# ShieldArduino_Due_5.net
KiCad netlist of a schematic drawn in Altium Designer
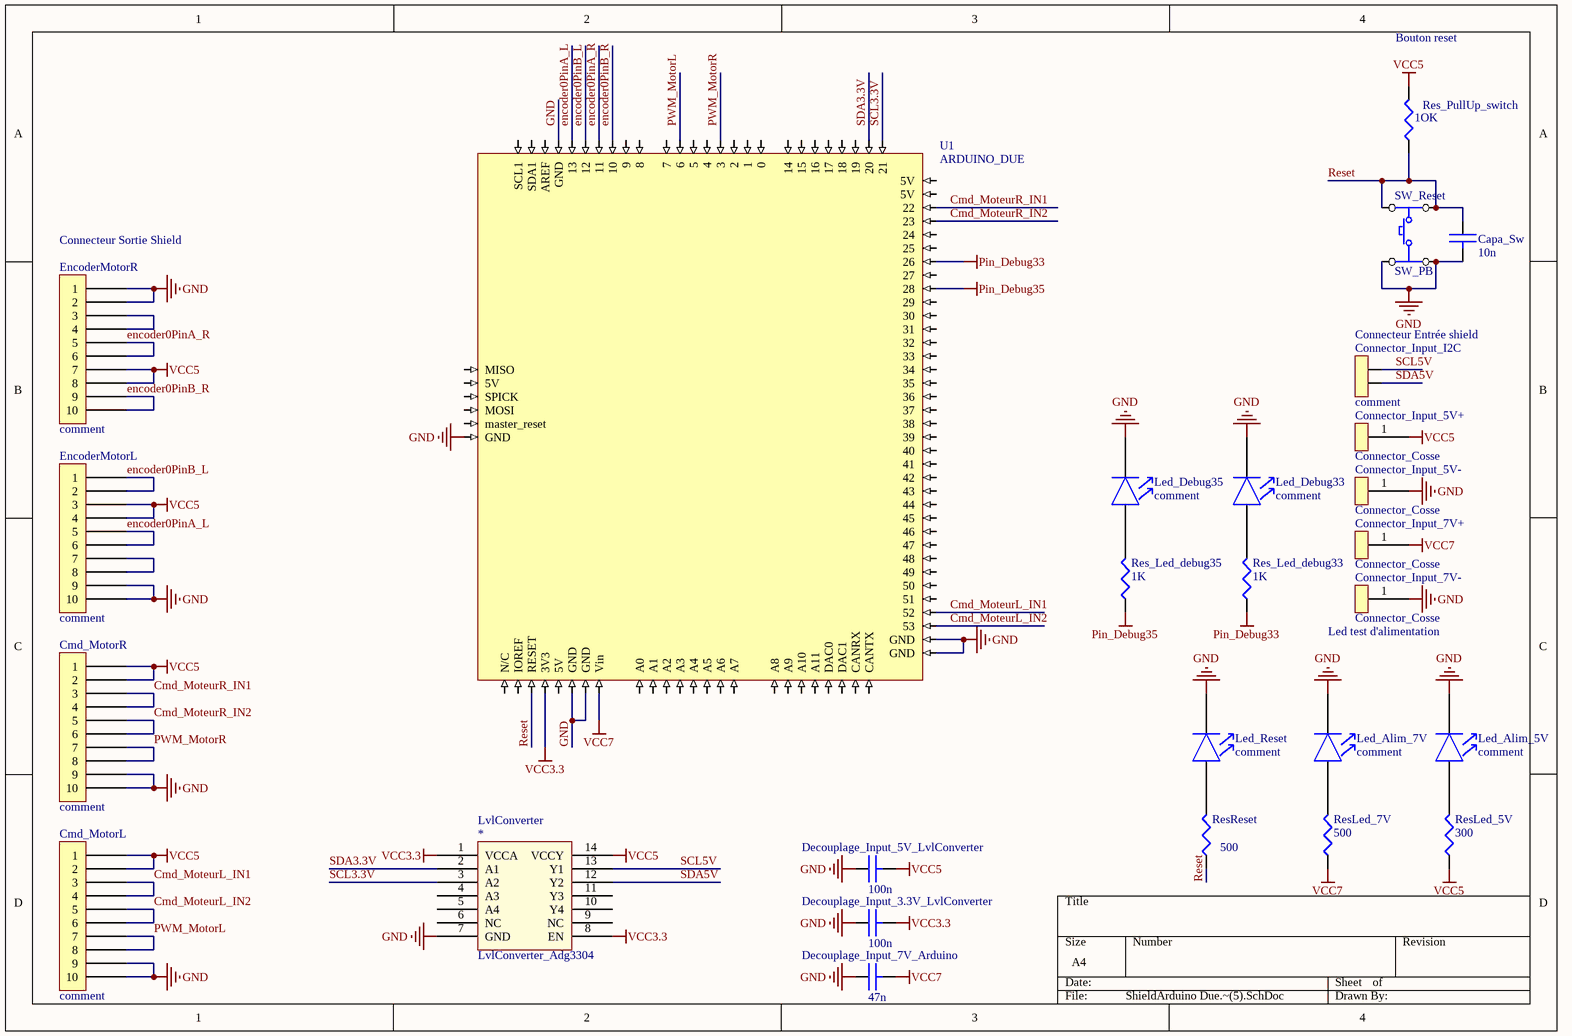
[diagram p0: ShieldArduino Due.~(5).SchDoc]

(export (version "E")
  (design (tool "Eeschema 10.0.6"))
  (components
    (comp (ref "*")
      (value "LvlConverter_Adg3304")
      (footprint "LvlConverter_Adg3304")
      (libsource (lib "LvlConverter_Adg3304") (part "LvlConverter_Adg3304"))
    )
    (comp (ref "Capa_Sw")
      (value "10n")
      (footprint "0805")
      (description "capacité non polarisée")
      (fields (field (name "Comment") "CAP"))
      (libsource (lib "ISEN_basics") (part "CAP"))
    )
    (comp (ref "Cmd_MotorL")
      (value "comment")
      (footprint "HE10-10V")
      (description "10-pin connector")
      (libsource (lib "ISEN_basics") (part "HE10-10"))
    )
    (comp (ref "Cmd_MotorR")
      (value "comment")
      (footprint "HE10-10V")
      (description "10-pin connector")
      (libsource (lib "ISEN_basics") (part "HE10-10"))
    )
    (comp (ref "Connector_Input_5V+")
      (value "Connector_Cosse")
      (footprint "Connector_Cosse")
      (libsource (lib "Connector_Cosse") (part "Connector_Cosse"))
    )
    (comp (ref "Connector_Input_5V-")
      (value "Connector_Cosse")
      (footprint "Connector_Cosse")
      (libsource (lib "Connector_Cosse") (part "Connector_Cosse"))
    )
    (comp (ref "Connector_Input_7V+")
      (value "Connector_Cosse")
      (footprint "Connector_Cosse")
      (libsource (lib "Connector_Cosse") (part "Connector_Cosse"))
    )
    (comp (ref "Connector_Input_7V-")
      (value "Connector_Cosse")
      (footprint "Connector_Cosse")
      (libsource (lib "Connector_Cosse") (part "Connector_Cosse"))
    )
    (comp (ref "Connector_Input_I2C")
      (value "comment")
      (footprint "AMP_2")
      (description "connecteur alim 2 pôles")
      (libsource (lib "ISEN_basics") (part "POWER2"))
    )
    (comp (ref "Decouplage_Input_3.3V_LvlConverter")
      (value "100n")
      (footprint "0805")
      (description "capacité non polarisée")
      (fields (field (name "Comment") "CAP"))
      (libsource (lib "ISEN_basics") (part "CAP"))
    )
    (comp (ref "Decouplage_Input_5V_LvlConverter")
      (value "100n")
      (footprint "0805")
      (description "capacité non polarisée")
      (fields (field (name "Comment") "CAP"))
      (libsource (lib "ISEN_basics") (part "CAP"))
    )
    (comp (ref "Decouplage_Input_7V_Arduino")
      (value "47n")
      (footprint "0805")
      (description "capacité non polarisée")
      (fields (field (name "Comment") "CAP"))
      (libsource (lib "ISEN_basics") (part "CAP"))
    )
    (comp (ref "EncoderMotorL")
      (value "comment")
      (footprint "HE10-10V")
      (description "10-pin connector")
      (libsource (lib "ISEN_basics") (part "HE10-10"))
    )
    (comp (ref "EncoderMotorR")
      (value "comment")
      (footprint "HE10-10V")
      (description "10-pin connector")
      (libsource (lib "ISEN_basics") (part "HE10-10"))
    )
    (comp (ref "Led_Alim_5V")
      (value "comment")
      (footprint "LED0805")
      (description "LED 5mm/3mm/CMS")
      (libsource (lib "ISEN_basics") (part "LED"))
    )
    (comp (ref "Led_Alim_7V")
      (value "comment")
      (footprint "LED0805")
      (description "LED 5mm/3mm/CMS")
      (libsource (lib "ISEN_basics") (part "LED"))
    )
    (comp (ref "Led_Debug33")
      (value "comment")
      (footprint "LED0805")
      (description "LED 5mm/3mm/CMS")
      (libsource (lib "ISEN_basics") (part "LED"))
    )
    (comp (ref "Led_Debug35")
      (value "comment")
      (footprint "LED0805")
      (description "LED 5mm/3mm/CMS")
      (libsource (lib "ISEN_basics") (part "LED"))
    )
    (comp (ref "Led_Reset")
      (value "comment")
      (footprint "LED0805")
      (description "LED 5mm/3mm/CMS")
      (libsource (lib "ISEN_basics") (part "LED"))
    )
    (comp (ref "ResLed_5V")
      (value "300")
      (footprint "0805")
      (description "resistance")
      (fields (field (name "Comment") "RES"))
      (libsource (lib "ISEN_basics") (part "RES"))
    )
    (comp (ref "ResLed_7V")
      (value "500")
      (footprint "0805")
      (description "resistance")
      (fields (field (name "Comment") "RES"))
      (libsource (lib "ISEN_basics") (part "RES"))
    )
    (comp (ref "ResReset")
      (value "500")
      (footprint "0805")
      (description "resistance")
      (fields (field (name "Comment") "RES"))
      (libsource (lib "ISEN_basics") (part "RES"))
    )
    (comp (ref "Res_Led_debug33")
      (value "1K")
      (footprint "0805")
      (description "resistance")
      (fields (field (name "Comment") "RES"))
      (libsource (lib "ISEN_basics") (part "RES"))
    )
    (comp (ref "Res_Led_debug35")
      (value "1K")
      (footprint "0805")
      (description "resistance")
      (fields (field (name "Comment") "RES"))
      (libsource (lib "ISEN_basics") (part "RES"))
    )
    (comp (ref "Res_PullUp_switch")
      (value "1OK")
      (footprint "0805")
      (description "resistance")
      (fields (field (name "Comment") "RES"))
      (libsource (lib "ISEN_basics") (part "RES"))
    )
    (comp (ref "SW_Reset") (value "SW_PB") (footprint "KSA") (libsource (lib "ISEN_basics") (part "SW_PB")))
    (comp (ref "U1")
      (value "ARDUINO_DUE")
      (footprint "ARDUINO_DUE")
      (libsource (lib "ISEN_basics") (part "ARDUINO_DUE"))
    )
  )
  (nets
    (net (code "1") (name "/Cmd_MoteurL_IN1") (class "Default")
      (node (ref "Cmd_MotorL") (pin "3") (pinfunction "3_3") (pintype "passive"))
      (node (ref "Cmd_MotorL") (pin "4") (pinfunction "4_4") (pintype "passive"))
      (node (ref "U1") (pin "59") (pinfunction "52_59") (pintype "input"))
    )
    (net (code "2") (name "/Cmd_MoteurL_IN2") (class "Default")
      (node (ref "Cmd_MotorL") (pin "5") (pinfunction "5_5") (pintype "passive"))
      (node (ref "Cmd_MotorL") (pin "6") (pinfunction "6_6") (pintype "passive"))
      (node (ref "U1") (pin "60") (pinfunction "53_60") (pintype "input"))
    )
    (net (code "3") (name "/Cmd_MoteurR_IN1") (class "Default")
      (node (ref "Cmd_MotorR") (pin "3") (pinfunction "3_3") (pintype "passive"))
      (node (ref "Cmd_MotorR") (pin "4") (pinfunction "4_4") (pintype "passive"))
      (node (ref "U1") (pin "29") (pinfunction "22_29") (pintype "input"))
    )
    (net (code "4") (name "/Cmd_MoteurR_IN2") (class "Default")
      (node (ref "Cmd_MotorR") (pin "5") (pinfunction "5_5") (pintype "passive"))
      (node (ref "Cmd_MotorR") (pin "6") (pinfunction "6_6") (pintype "passive"))
      (node (ref "U1") (pin "30") (pinfunction "23_30") (pintype "input"))
    )
    (net (code "5") (name "/PWM_MotorL") (class "Default")
      (node (ref "Cmd_MotorL") (pin "7") (pinfunction "7_7") (pintype "passive"))
      (node (ref "Cmd_MotorL") (pin "8") (pinfunction "8_8") (pintype "passive"))
      (node (ref "U1") (pin "12") (pinfunction "6_12") (pintype "input"))
    )
    (net (code "6") (name "/PWM_MotorR") (class "Default")
      (node (ref "Cmd_MotorR") (pin "7") (pinfunction "7_7") (pintype "passive"))
      (node (ref "Cmd_MotorR") (pin "8") (pinfunction "8_8") (pintype "passive"))
      (node (ref "U1") (pin "15") (pinfunction "3_15") (pintype "input"))
    )
    (net (code "7") (name "/Reset") (class "Default")
      (node (ref "Capa_Sw") (pin "1") (pinfunction "1_1") (pintype "passive"))
      (node (ref "ResReset") (pin "1") (pintype "passive"))
      (node (ref "Res_PullUp_switch") (pin "1") (pintype "passive"))
      (node (ref "SW_Reset") (pin "3") (pintype "passive"))
      (node (ref "SW_Reset") (pin "4") (pintype "passive"))
      (node (ref "U1") (pin "84") (pinfunction "RESET_84") (pintype "input"))
    )
    (net (code "8") (name "/SCL3.3V") (class "Default")
      (node (ref "*") (pin "3") (pinfunction "A2_3") (pintype "power_in"))
      (node (ref "U1") (pin "26") (pinfunction "21_26") (pintype "input"))
    )
    (net (code "9") (name "/SCL5V") (class "Default")
      (node (ref "*") (pin "13") (pinfunction "Y1_13") (pintype "power_in"))
      (node (ref "Connector_Input_I2C") (pin "1") (pintype "passive"))
    )
    (net (code "10") (name "/SDA3.3V") (class "Default")
      (node (ref "*") (pin "2") (pinfunction "A1_2") (pintype "power_in"))
      (node (ref "U1") (pin "25") (pinfunction "20_25") (pintype "input"))
    )
    (net (code "11") (name "/SDA5V") (class "Default")
      (node (ref "*") (pin "12") (pinfunction "Y2_12") (pintype "power_in"))
      (node (ref "Connector_Input_I2C") (pin "2") (pintype "passive"))
    )
    (net (code "12") (name "/encoder0PinA_L") (class "Default")
      (node (ref "EncoderMotorL") (pin "5") (pinfunction "5_5") (pintype "passive"))
      (node (ref "EncoderMotorL") (pin "6") (pinfunction "6_6") (pintype "passive"))
      (node (ref "U1") (pin "5") (pinfunction "13_5") (pintype "input"))
    )
    (net (code "13") (name "/encoder0PinA_R") (class "Default")
      (node (ref "EncoderMotorR") (pin "5") (pinfunction "5_5") (pintype "passive"))
      (node (ref "EncoderMotorR") (pin "6") (pinfunction "6_6") (pintype "passive"))
      (node (ref "U1") (pin "7") (pinfunction "11_7") (pintype "input"))
    )
    (net (code "14") (name "/encoder0PinB_L") (class "Default")
      (node (ref "EncoderMotorL") (pin "1") (pinfunction "1_1") (pintype "passive"))
      (node (ref "EncoderMotorL") (pin "2") (pinfunction "2_2") (pintype "passive"))
      (node (ref "U1") (pin "6") (pinfunction "12_6") (pintype "input"))
    )
    (net (code "15") (name "/encoder0PinB_R") (class "Default")
      (node (ref "EncoderMotorR") (pin "10") (pinfunction "10_10") (pintype "passive"))
      (node (ref "EncoderMotorR") (pin "9") (pinfunction "9_9") (pintype "passive"))
      (node (ref "U1") (pin "8") (pinfunction "10_8") (pintype "input"))
    )
    (net (code "16") (name "GND") (class "Default")
      (node (ref "*") (pin "7") (pinfunction "GND_7") (pintype "power_in"))
      (node (ref "Capa_Sw") (pin "2") (pinfunction "2_2") (pintype "passive"))
      (node (ref "Cmd_MotorL") (pin "10") (pinfunction "10_10") (pintype "passive"))
      (node (ref "Cmd_MotorL") (pin "9") (pinfunction "9_9") (pintype "passive"))
      (node (ref "Cmd_MotorR") (pin "10") (pinfunction "10_10") (pintype "passive"))
      (node (ref "Cmd_MotorR") (pin "9") (pinfunction "9_9") (pintype "passive"))
      (node (ref "Connector_Input_5V-") (pin "1") (pintype "passive"))
      (node (ref "Connector_Input_7V-") (pin "1") (pintype "passive"))
      (node (ref "Decouplage_Input_3.3V_LvlConverter") (pin "1") (pinfunction "1_1") (pintype "passive"))
      (node (ref "Decouplage_Input_5V_LvlConverter") (pin "1") (pinfunction "1_1") (pintype "passive"))
      (node (ref "Decouplage_Input_7V_Arduino") (pin "1") (pinfunction "1_1") (pintype "passive"))
      (node (ref "EncoderMotorL") (pin "10") (pinfunction "10_10") (pintype "passive"))
      (node (ref "EncoderMotorL") (pin "9") (pinfunction "9_9") (pintype "passive"))
      (node (ref "EncoderMotorR") (pin "1") (pinfunction "1_1") (pintype "passive"))
      (node (ref "EncoderMotorR") (pin "2") (pinfunction "2_2") (pintype "passive"))
      (node (ref "Led_Alim_5V") (pin "K") (pinfunction "10_K") (pintype "passive"))
      (node (ref "Led_Alim_7V") (pin "K") (pinfunction "10_K") (pintype "passive"))
      (node (ref "Led_Debug33") (pin "K") (pinfunction "10_K") (pintype "passive"))
      (node (ref "Led_Debug35") (pin "K") (pinfunction "10_K") (pintype "passive"))
      (node (ref "Led_Reset") (pin "K") (pinfunction "10_K") (pintype "passive"))
      (node (ref "SW_Reset") (pin "1") (pintype "passive"))
      (node (ref "SW_Reset") (pin "2") (pintype "passive"))
      (node (ref "U1") (pin "4") (pinfunction "GND_4") (pintype "input"))
      (node (ref "U1") (pin "61") (pinfunction "GND_61") (pintype "input"))
      (node (ref "U1") (pin "62") (pinfunction "GND_62") (pintype "input"))
      (node (ref "U1") (pin "80") (pinfunction "GND_80") (pintype "input"))
      (node (ref "U1") (pin "81") (pinfunction "GND_81") (pintype "input"))
      (node (ref "U1") (pin "92") (pinfunction "GND_92") (pintype "input"))
    )
    (net (code "17") (name "Net-(EncoderMotorL-Pad7)") (class "Default")
      (node (ref "EncoderMotorL") (pin "7") (pinfunction "7_7") (pintype "passive"))
      (node (ref "EncoderMotorL") (pin "8") (pinfunction "8_8") (pintype "passive"))
    )
    (net (code "18") (name "Net-(EncoderMotorR-Pad3)") (class "Default")
      (node (ref "EncoderMotorR") (pin "3") (pinfunction "3_3") (pintype "passive"))
      (node (ref "EncoderMotorR") (pin "4") (pinfunction "4_4") (pintype "passive"))
    )
    (net (code "19") (name "Net-(Led_Alim_5V-8)") (class "Default")
      (node (ref "Led_Alim_5V") (pin "A") (pinfunction "8_A") (pintype "passive"))
      (node (ref "ResLed_5V") (pin "2") (pintype "passive"))
    )
    (net (code "20") (name "Net-(Led_Alim_7V-8)") (class "Default")
      (node (ref "Led_Alim_7V") (pin "A") (pinfunction "8_A") (pintype "passive"))
      (node (ref "ResLed_7V") (pin "2") (pintype "passive"))
    )
    (net (code "21") (name "Net-(Led_Debug33-8)") (class "Default")
      (node (ref "Led_Debug33") (pin "A") (pinfunction "8_A") (pintype "passive"))
      (node (ref "Res_Led_debug33") (pin "2") (pintype "passive"))
    )
    (net (code "22") (name "Net-(Led_Debug35-8)") (class "Default")
      (node (ref "Led_Debug35") (pin "A") (pinfunction "8_A") (pintype "passive"))
      (node (ref "Res_Led_debug35") (pin "2") (pintype "passive"))
    )
    (net (code "23") (name "Net-(Led_Reset-8)") (class "Default")
      (node (ref "Led_Reset") (pin "A") (pinfunction "8_A") (pintype "passive"))
      (node (ref "ResReset") (pin "2") (pintype "passive"))
    )
    (net (code "24") (name "Pin_Debug33") (class "Default")
      (node (ref "Res_Led_debug33") (pin "1") (pintype "passive"))
      (node (ref "U1") (pin "33") (pinfunction "26_33") (pintype "input"))
    )
    (net (code "25") (name "Pin_Debug35") (class "Default")
      (node (ref "Res_Led_debug35") (pin "1") (pintype "passive"))
      (node (ref "U1") (pin "35") (pinfunction "28_35") (pintype "input"))
    )
    (net (code "26") (name "VCC3.3") (class "Default")
      (node (ref "*") (pin "1") (pinfunction "VCCA_1") (pintype "power_in"))
      (node (ref "*") (pin "8") (pinfunction "EN_8") (pintype "power_in"))
      (node (ref "Decouplage_Input_3.3V_LvlConverter") (pin "2") (pinfunction "2_2") (pintype "passive"))
      (node (ref "U1") (pin "83") (pinfunction "3V3_83") (pintype "input"))
    )
    (net (code "27") (name "VCC5") (class "Default")
      (node (ref "*") (pin "14") (pinfunction "VCCY_14") (pintype "power_in"))
      (node (ref "Cmd_MotorL") (pin "1") (pinfunction "1_1") (pintype "passive"))
      (node (ref "Cmd_MotorL") (pin "2") (pinfunction "2_2") (pintype "passive"))
      (node (ref "Cmd_MotorR") (pin "1") (pinfunction "1_1") (pintype "passive"))
      (node (ref "Cmd_MotorR") (pin "2") (pinfunction "2_2") (pintype "passive"))
      (node (ref "Connector_Input_5V+") (pin "1") (pintype "passive"))
      (node (ref "Decouplage_Input_5V_LvlConverter") (pin "2") (pinfunction "2_2") (pintype "passive"))
      (node (ref "EncoderMotorL") (pin "3") (pinfunction "3_3") (pintype "passive"))
      (node (ref "EncoderMotorL") (pin "4") (pinfunction "4_4") (pintype "passive"))
      (node (ref "EncoderMotorR") (pin "7") (pinfunction "7_7") (pintype "passive"))
      (node (ref "EncoderMotorR") (pin "8") (pinfunction "8_8") (pintype "passive"))
      (node (ref "ResLed_5V") (pin "1") (pintype "passive"))
      (node (ref "Res_PullUp_switch") (pin "2") (pintype "passive"))
    )
    (net (code "28") (name "VCC7") (class "Default")
      (node (ref "Connector_Input_7V+") (pin "1") (pintype "passive"))
      (node (ref "Decouplage_Input_7V_Arduino") (pin "2") (pinfunction "2_2") (pintype "passive"))
      (node (ref "ResLed_7V") (pin "1") (pintype "passive"))
      (node (ref "U1") (pin "79") (pinfunction "Vin_79") (pintype "input"))
    )
    (net (code "29") (name "unconnected-(*-A3-Pad4)") (class "Default")
      (node (ref "*") (pin "4") (pinfunction "A3_4") (pintype "power_in"))
    )
    (net (code "30") (name "unconnected-(*-A4-Pad5)") (class "Default")
      (node (ref "*") (pin "5") (pinfunction "A4_5") (pintype "power_in"))
    )
    (net (code "31") (name "unconnected-(*-NC-Pad6)") (class "Default")
      (node (ref "*") (pin "6") (pinfunction "NC_6") (pintype "power_in"))
    )
    (net (code "32") (name "unconnected-(*-NC-Pad9)") (class "Default")
      (node (ref "*") (pin "9") (pinfunction "NC_9") (pintype "power_in"))
    )
    (net (code "33") (name "unconnected-(*-Y3-Pad11)") (class "Default")
      (node (ref "*") (pin "11") (pinfunction "Y3_11") (pintype "power_in"))
    )
    (net (code "34") (name "unconnected-(*-Y4-Pad10)") (class "Default")
      (node (ref "*") (pin "10") (pinfunction "Y4_10") (pintype "power_in"))
    )
    (net (code "35") (name "unconnected-(U1-0-Pad18)") (class "Default")
      (node (ref "U1") (pin "18") (pinfunction "0_18") (pintype "input"))
    )
    (net (code "36") (name "unconnected-(U1-1-Pad17)") (class "Default")
      (node (ref "U1") (pin "17") (pinfunction "1_17") (pintype "input"))
    )
    (net (code "37") (name "unconnected-(U1-2-Pad16)") (class "Default")
      (node (ref "U1") (pin "16") (pinfunction "2_16") (pintype "input"))
    )
    (net (code "38") (name "unconnected-(U1-4-Pad14)") (class "Default")
      (node (ref "U1") (pin "14") (pinfunction "4_14") (pintype "input"))
    )
    (net (code "39") (name "unconnected-(U1-5-Pad13)") (class "Default")
      (node (ref "U1") (pin "13") (pinfunction "5_13") (pintype "input"))
    )
    (net (code "40") (name "unconnected-(U1-5V-Pad27)") (class "Default")
      (node (ref "U1") (pin "27") (pinfunction "5V_27") (pintype "input"))
    )
    (net (code "41") (name "unconnected-(U1-5V-Pad28)") (class "Default")
      (node (ref "U1") (pin "28") (pinfunction "5V_28") (pintype "input"))
    )
    (net (code "42") (name "unconnected-(U1-5V-Pad82)") (class "Default")
      (node (ref "U1") (pin "82") (pinfunction "5V_82") (pintype "input"))
    )
    (net (code "43") (name "unconnected-(U1-5V-Pad88)") (class "Default")
      (node (ref "U1") (pin "88") (pinfunction "5V_88") (pintype "input"))
    )
    (net (code "44") (name "unconnected-(U1-7-Pad11)") (class "Default")
      (node (ref "U1") (pin "11") (pinfunction "7_11") (pintype "input"))
    )
    (net (code "45") (name "unconnected-(U1-8-Pad10)") (class "Default")
      (node (ref "U1") (pin "10") (pinfunction "8_10") (pintype "input"))
    )
    (net (code "46") (name "unconnected-(U1-14-Pad19)") (class "Default")
      (node (ref "U1") (pin "19") (pinfunction "14_19") (pintype "input"))
    )
    (net (code "47") (name "unconnected-(U1-15-Pad20)") (class "Default")
      (node (ref "U1") (pin "20") (pinfunction "15_20") (pintype "input"))
    )
    (net (code "48") (name "unconnected-(U1-16-Pad21)") (class "Default")
      (node (ref "U1") (pin "21") (pinfunction "16_21") (pintype "input"))
    )
    (net (code "49") (name "unconnected-(U1-17-Pad22)") (class "Default")
      (node (ref "U1") (pin "22") (pinfunction "17_22") (pintype "input"))
    )
    (net (code "50") (name "unconnected-(U1-18-Pad23)") (class "Default")
      (node (ref "U1") (pin "23") (pinfunction "18_23") (pintype "input"))
    )
    (net (code "51") (name "unconnected-(U1-19-Pad24)") (class "Default")
      (node (ref "U1") (pin "24") (pinfunction "19_24") (pintype "input"))
    )
    (net (code "52") (name "unconnected-(U1-24-Pad31)") (class "Default")
      (node (ref "U1") (pin "31") (pinfunction "24_31") (pintype "input"))
    )
    (net (code "53") (name "unconnected-(U1-25-Pad32)") (class "Default")
      (node (ref "U1") (pin "32") (pinfunction "25_32") (pintype "input"))
    )
    (net (code "54") (name "unconnected-(U1-27-Pad34)") (class "Default")
      (node (ref "U1") (pin "34") (pinfunction "27_34") (pintype "input"))
    )
    (net (code "55") (name "unconnected-(U1-29-Pad36)") (class "Default")
      (node (ref "U1") (pin "36") (pinfunction "29_36") (pintype "input"))
    )
    (net (code "56") (name "unconnected-(U1-30-Pad37)") (class "Default")
      (node (ref "U1") (pin "37") (pinfunction "30_37") (pintype "input"))
    )
    (net (code "57") (name "unconnected-(U1-31-Pad38)") (class "Default")
      (node (ref "U1") (pin "38") (pinfunction "31_38") (pintype "input"))
    )
    (net (code "58") (name "unconnected-(U1-32-Pad39)") (class "Default")
      (node (ref "U1") (pin "39") (pinfunction "32_39") (pintype "input"))
    )
    (net (code "59") (name "unconnected-(U1-33-Pad40)") (class "Default")
      (node (ref "U1") (pin "40") (pinfunction "33_40") (pintype "input"))
    )
    (net (code "60") (name "unconnected-(U1-34-Pad41)") (class "Default")
      (node (ref "U1") (pin "41") (pinfunction "34_41") (pintype "input"))
    )
    (net (code "61") (name "unconnected-(U1-35-Pad42)") (class "Default")
      (node (ref "U1") (pin "42") (pinfunction "35_42") (pintype "input"))
    )
    (net (code "62") (name "unconnected-(U1-36-Pad43)") (class "Default")
      (node (ref "U1") (pin "43") (pinfunction "36_43") (pintype "input"))
    )
    (net (code "63") (name "unconnected-(U1-37-Pad44)") (class "Default")
      (node (ref "U1") (pin "44") (pinfunction "37_44") (pintype "input"))
    )
    (net (code "64") (name "unconnected-(U1-38-Pad45)") (class "Default")
      (node (ref "U1") (pin "45") (pinfunction "38_45") (pintype "input"))
    )
    (net (code "65") (name "unconnected-(U1-39-Pad46)") (class "Default")
      (node (ref "U1") (pin "46") (pinfunction "39_46") (pintype "input"))
    )
    (net (code "66") (name "unconnected-(U1-40-Pad47)") (class "Default")
      (node (ref "U1") (pin "47") (pinfunction "40_47") (pintype "input"))
    )
    (net (code "67") (name "unconnected-(U1-41-Pad48)") (class "Default")
      (node (ref "U1") (pin "48") (pinfunction "41_48") (pintype "input"))
    )
    (net (code "68") (name "unconnected-(U1-42-Pad49)") (class "Default")
      (node (ref "U1") (pin "49") (pinfunction "42_49") (pintype "input"))
    )
    (net (code "69") (name "unconnected-(U1-43-Pad50)") (class "Default")
      (node (ref "U1") (pin "50") (pinfunction "43_50") (pintype "input"))
    )
    (net (code "70") (name "unconnected-(U1-44-Pad51)") (class "Default")
      (node (ref "U1") (pin "51") (pinfunction "44_51") (pintype "input"))
    )
    (net (code "71") (name "unconnected-(U1-45-Pad52)") (class "Default")
      (node (ref "U1") (pin "52") (pinfunction "45_52") (pintype "input"))
    )
    (net (code "72") (name "unconnected-(U1-46-Pad53)") (class "Default")
      (node (ref "U1") (pin "53") (pinfunction "46_53") (pintype "input"))
    )
    (net (code "73") (name "unconnected-(U1-47-Pad54)") (class "Default")
      (node (ref "U1") (pin "54") (pinfunction "47_54") (pintype "input"))
    )
    (net (code "74") (name "unconnected-(U1-48-Pad55)") (class "Default")
      (node (ref "U1") (pin "55") (pinfunction "48_55") (pintype "input"))
    )
    (net (code "75") (name "unconnected-(U1-49-Pad56)") (class "Default")
      (node (ref "U1") (pin "56") (pinfunction "49_56") (pintype "input"))
    )
    (net (code "76") (name "unconnected-(U1-50-Pad57)") (class "Default")
      (node (ref "U1") (pin "57") (pinfunction "50_57") (pintype "input"))
    )
    (net (code "77") (name "unconnected-(U1-51-Pad58)") (class "Default")
      (node (ref "U1") (pin "58") (pinfunction "51_58") (pintype "input"))
    )
    (net (code "78") (name "unconnected-(U1-A0-Pad78)") (class "Default")
      (node (ref "U1") (pin "78") (pinfunction "A0_78") (pintype "input"))
    )
    (net (code "79") (name "unconnected-(U1-A1-Pad77)") (class "Default")
      (node (ref "U1") (pin "77") (pinfunction "A1_77") (pintype "input"))
    )
    (net (code "80") (name "unconnected-(U1-A2-Pad76)") (class "Default")
      (node (ref "U1") (pin "76") (pinfunction "A2_76") (pintype "input"))
    )
    (net (code "81") (name "unconnected-(U1-A3-Pad75)") (class "Default")
      (node (ref "U1") (pin "75") (pinfunction "A3_75") (pintype "input"))
    )
    (net (code "82") (name "unconnected-(U1-A4-Pad74)") (class "Default")
      (node (ref "U1") (pin "74") (pinfunction "A4_74") (pintype "input"))
    )
    (net (code "83") (name "unconnected-(U1-A5-Pad73)") (class "Default")
      (node (ref "U1") (pin "73") (pinfunction "A5_73") (pintype "input"))
    )
    (net (code "84") (name "unconnected-(U1-A6-Pad72)") (class "Default")
      (node (ref "U1") (pin "72") (pinfunction "A6_72") (pintype "input"))
    )
    (net (code "85") (name "unconnected-(U1-A7-Pad71)") (class "Default")
      (node (ref "U1") (pin "71") (pinfunction "A7_71") (pintype "input"))
    )
    (net (code "86") (name "unconnected-(U1-A8-Pad70)") (class "Default")
      (node (ref "U1") (pin "70") (pinfunction "A8_70") (pintype "input"))
    )
    (net (code "87") (name "unconnected-(U1-A9-Pad69)") (class "Default")
      (node (ref "U1") (pin "69") (pinfunction "A9_69") (pintype "input"))
    )
    (net (code "88") (name "unconnected-(U1-A10-Pad68)") (class "Default")
      (node (ref "U1") (pin "68") (pinfunction "A10_68") (pintype "input"))
    )
    (net (code "89") (name "unconnected-(U1-A11-Pad67)") (class "Default")
      (node (ref "U1") (pin "67") (pinfunction "A11_67") (pintype "input"))
    )
    (net (code "90") (name "unconnected-(U1-AREF-Pad3)") (class "Default")
      (node (ref "U1") (pin "3") (pinfunction "AREF_3") (pintype "input"))
    )
    (net (code "91") (name "unconnected-(U1-CANRX-Pad64)") (class "Default")
      (node (ref "U1") (pin "64") (pinfunction "CANRX_64") (pintype "input"))
    )
    (net (code "92") (name "unconnected-(U1-CANTX-Pad63)") (class "Default")
      (node (ref "U1") (pin "63") (pinfunction "CANTX_63") (pintype "input"))
    )
    (net (code "93") (name "unconnected-(U1-DAC0-Pad66)") (class "Default")
      (node (ref "U1") (pin "66") (pinfunction "DAC0_66") (pintype "input"))
    )
    (net (code "94") (name "unconnected-(U1-DAC1-Pad65)") (class "Default")
      (node (ref "U1") (pin "65") (pinfunction "DAC1_65") (pintype "input"))
    )
    (net (code "95") (name "unconnected-(U1-IOREF-Pad85)") (class "Default")
      (node (ref "U1") (pin "85") (pinfunction "IOREF_85") (pintype "input"))
    )
    (net (code "96") (name "unconnected-(U1-MISO-Pad87)") (class "Default")
      (node (ref "U1") (pin "87") (pinfunction "MISO_87") (pintype "input"))
    )
    (net (code "97") (name "unconnected-(U1-MOSI-Pad90)") (class "Default")
      (node (ref "U1") (pin "90") (pinfunction "MOSI_90") (pintype "input"))
    )
    (net (code "98") (name "unconnected-(U1-N{slash}C-Pad86)") (class "Default")
      (node (ref "U1") (pin "86") (pinfunction "N/C_86") (pintype "input"))
    )
    (net (code "99") (name "unconnected-(U1-Pad9)") (class "Default")
      (node (ref "U1") (pin "9") (pinfunction "9_9") (pintype "input"))
    )
    (net (code "100") (name "unconnected-(U1-SCL1-Pad1)") (class "Default")
      (node (ref "U1") (pin "1") (pinfunction "SCL1_1") (pintype "input"))
    )
    (net (code "101") (name "unconnected-(U1-SDA1-Pad2)") (class "Default")
      (node (ref "U1") (pin "2") (pinfunction "SDA1_2") (pintype "input"))
    )
    (net (code "102") (name "unconnected-(U1-SPICK-Pad89)") (class "Default")
      (node (ref "U1") (pin "89") (pinfunction "SPICK_89") (pintype "input"))
    )
    (net (code "103") (name "unconnected-(U1-master_reset-Pad91)") (class "Default")
      (node (ref "U1") (pin "91") (pinfunction "master_reset_91") (pintype "input"))
    )
  )
)
